# sum_rev1_4.net
KiCad netlist of a schematic drawn in EAGLE
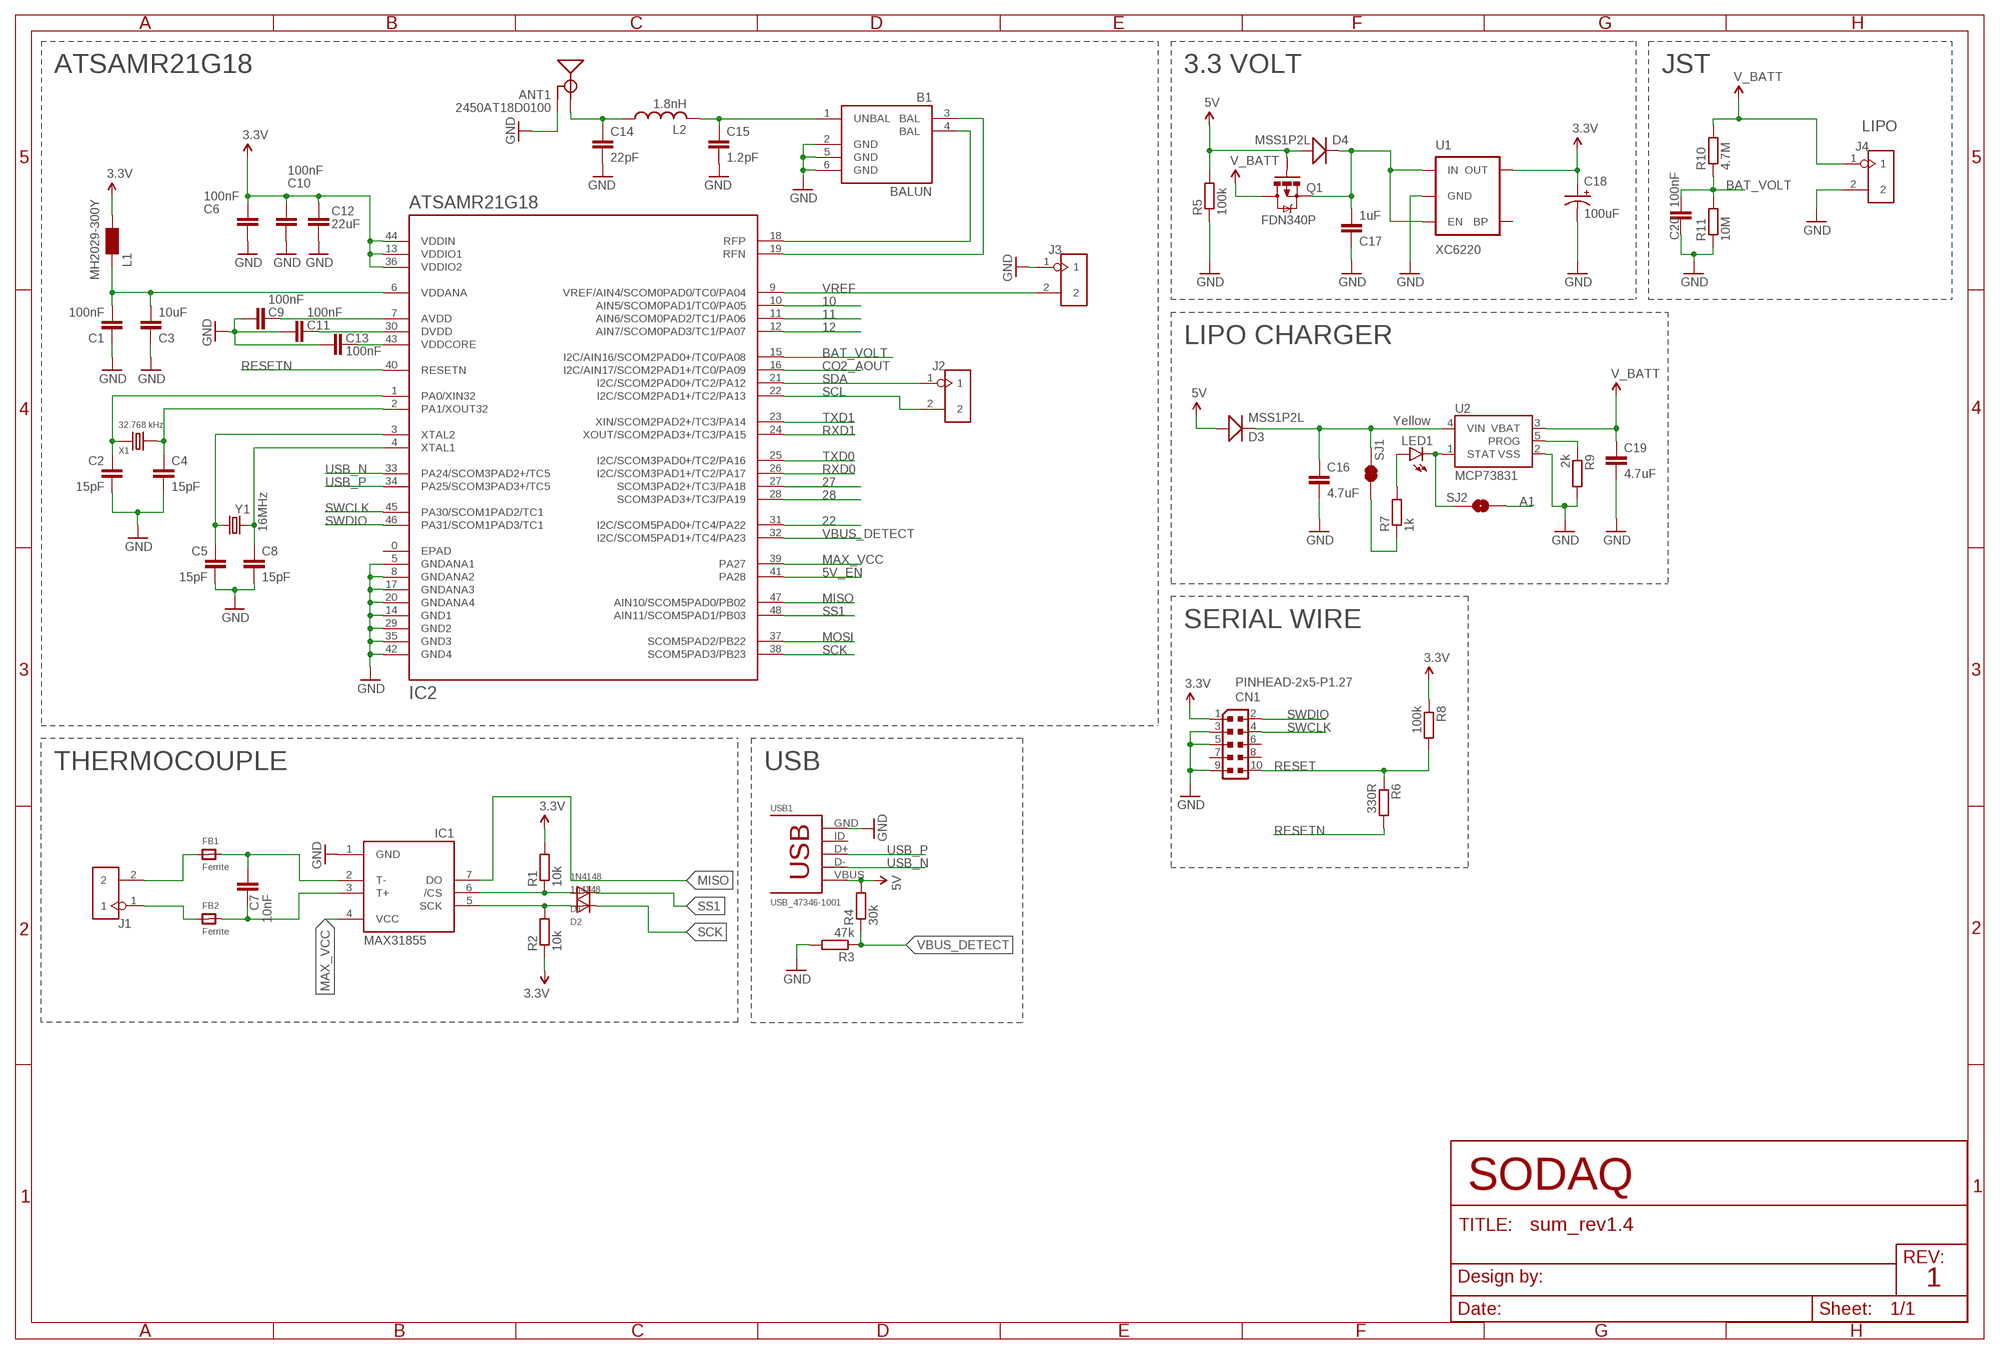
[diagram p0: schematic, sheet 1]

(export (version "E")
  (design (tool "Eeschema 10.0.6"))
  (components
    (comp (ref "ANT1")
      (value "2450AT18D0100")
      (footprint "eagle-import:2450AT18D0100")
      (libsource (lib "eagle-import") (part "2450AT18D0100"))
    )
    (comp (ref "B1")
      (value "BALUN")
      (footprint "eagle-import:BALUN")
      (libsource (lib "eagle-import") (part "BALUN"))
    )
    (comp (ref "C1")
      (value "100nF")
      (footprint "eagle-import:C0402")
      (libsource (lib "eagle-import") (part "C_0402"))
    )
    (comp (ref "C2")
      (value "15pF")
      (footprint "eagle-import:C0402")
      (libsource (lib "eagle-import") (part "C_0402"))
    )
    (comp (ref "C3")
      (value "10uF")
      (footprint "eagle-import:C0402")
      (libsource (lib "eagle-import") (part "C_0402"))
    )
    (comp (ref "C4")
      (value "15pF")
      (footprint "eagle-import:C0402")
      (libsource (lib "eagle-import") (part "C_0402"))
    )
    (comp (ref "C5")
      (value "15pF")
      (footprint "eagle-import:C0402")
      (libsource (lib "eagle-import") (part "C_0402"))
    )
    (comp (ref "C6")
      (value "100nF")
      (footprint "eagle-import:C0402")
      (libsource (lib "eagle-import") (part "C_0402"))
    )
    (comp (ref "C7")
      (value "10nF")
      (footprint "eagle-import:C0402")
      (libsource (lib "eagle-import") (part "C_0402"))
    )
    (comp (ref "C8")
      (value "15pF")
      (footprint "eagle-import:C0402")
      (libsource (lib "eagle-import") (part "C_0402"))
    )
    (comp (ref "C9")
      (value "100nF")
      (footprint "eagle-import:C0402")
      (libsource (lib "eagle-import") (part "C_0402"))
    )
    (comp (ref "C10")
      (value "100nF")
      (footprint "eagle-import:C0402")
      (libsource (lib "eagle-import") (part "C_0402"))
    )
    (comp (ref "C11")
      (value "100nF")
      (footprint "eagle-import:C0402")
      (libsource (lib "eagle-import") (part "C_0402"))
    )
    (comp (ref "C12")
      (value "22uF")
      (footprint "eagle-import:0805")
      (libsource (lib "eagle-import") (part "CAP0805"))
    )
    (comp (ref "C13")
      (value "100nF")
      (footprint "eagle-import:C0402")
      (libsource (lib "eagle-import") (part "C_0402"))
    )
    (comp (ref "C14")
      (value "22pF")
      (footprint "eagle-import:C0402")
      (libsource (lib "eagle-import") (part "C_0402"))
    )
    (comp (ref "C15")
      (value "1.2pF")
      (footprint "eagle-import:C0402")
      (libsource (lib "eagle-import") (part "C_0402"))
    )
    (comp (ref "C16")
      (value "4.7uF")
      (footprint "eagle-import:C0603")
      (libsource (lib "eagle-import") (part "C_0603"))
    )
    (comp (ref "C17")
      (value "1uF")
      (footprint "eagle-import:C0603")
      (libsource (lib "eagle-import") (part "C_0603"))
    )
    (comp (ref "C18")
      (value "100uF")
      (footprint "eagle-import:EIA3216")
      (libsource (lib "eagle-import") (part "CAP_POL1206"))
    )
    (comp (ref "C19")
      (value "4.7uF")
      (footprint "eagle-import:C0603")
      (libsource (lib "eagle-import") (part "C_0603"))
    )
    (comp (ref "C20")
      (value "100nF")
      (footprint "eagle-import:C0402")
      (libsource (lib "eagle-import") (part "C_0402"))
    )
    (comp (ref "CN1")
      (value "PINHEAD-2x5-P1.27")
      (footprint "eagle-import:PINHEAD_2X05_127")
      (libsource (lib "eagle-import") (part "0171_PH127-205DF055G00AROUND-PADS"))
    )
    (comp (ref "D1")
      (value "1N4148")
      (footprint "eagle-import:SOD-323F")
      (libsource (lib "eagle-import") (part "DIODESOD-323F"))
    )
    (comp (ref "D2")
      (value "1n4148")
      (footprint "eagle-import:SOD-323F")
      (libsource (lib "eagle-import") (part "DIODESOD-323F"))
    )
    (comp (ref "D3")
      (value "MSS1P2L")
      (footprint "eagle-import:D1005")
      (libsource (lib "eagle-import") (part "D'1005'"))
    )
    (comp (ref "D4")
      (value "MSS1P2L")
      (footprint "eagle-import:D1005")
      (libsource (lib "eagle-import") (part "D'1005'"))
    )
    (comp (ref "FB1")
      (value "Ferrite")
      (footprint "eagle-import:_0805")
      (libsource (lib "eagle-import") (part "FERRITE_0805"))
    )
    (comp (ref "FB2")
      (value "Ferrite")
      (footprint "eagle-import:_0805")
      (libsource (lib "eagle-import") (part "FERRITE_0805"))
    )
    (comp (ref "IC1")
      (value "MAX31855")
      (footprint "eagle-import:SO08")
      (libsource (lib "eagle-import") (part "MAX6675"))
    )
    (comp (ref "IC2")
      (value "ATSAMR21G18")
      (footprint "eagle-import:QFN48_SMALL-CPAD")
      (libsource (lib "eagle-import") (part "ATSAMR21G18"))
    )
    (comp (ref "J1")
      (value "HEADER-2P-2.0")
      (footprint "eagle-import:2P-2.0")
      (libsource (lib "eagle-import") (part "HEADER-2P-2.0"))
    )
    (comp (ref "J2")
      (value "HEADER-2P-2.0")
      (footprint "eagle-import:2P-2.0")
      (libsource (lib "eagle-import") (part "HEADER-2P-2.0"))
    )
    (comp (ref "J3")
      (value "HEADER-2P-2.0")
      (footprint "eagle-import:2P-2.0")
      (libsource (lib "eagle-import") (part "HEADER-2P-2.0"))
    )
    (comp (ref "J4")
      (value "HEADER-2P-2.0")
      (footprint "eagle-import:2P-2.0")
      (libsource (lib "eagle-import") (part "HEADER-2P-2.0"))
    )
    (comp (ref "L1")
      (value "MH2029-300Y")
      (footprint "eagle-import:0805")
      (fields (field (name "PART_NUMBER") "BLM21PG300SN1D_/_MH2029-300Y"))
      (libsource (lib "eagle-import") (part "0001_BLM21PG300SN1D_/_MH2029-300Y"))
    )
    (comp (ref "L2")
      (value "1.8nH")
      (footprint "eagle-import:L0402")
      (libsource (lib "eagle-import") (part "L_0402"))
    )
    (comp (ref "LED1")
      (value "Yellow")
      (footprint "eagle-import:LED-0603")
      (libsource (lib "eagle-import") (part "LED0603"))
    )
    (comp (ref "Q1")
      (value "FDN340P")
      (footprint "eagle-import:SOT23-S-PADS")
      (libsource (lib "eagle-import") (part "MOSFET-P-CHANNELSMALL"))
    )
    (comp (ref "R1")
      (value "10k")
      (footprint "eagle-import:R0402")
      (libsource (lib "eagle-import") (part "R_0402"))
    )
    (comp (ref "R2")
      (value "10k")
      (footprint "eagle-import:R0402")
      (libsource (lib "eagle-import") (part "R_0402"))
    )
    (comp (ref "R3")
      (value "47k")
      (footprint "eagle-import:R0402")
      (libsource (lib "eagle-import") (part "R_0402"))
    )
    (comp (ref "R4")
      (value "30k")
      (footprint "eagle-import:R0402")
      (libsource (lib "eagle-import") (part "R_0402"))
    )
    (comp (ref "R5")
      (value "100k")
      (footprint "eagle-import:R0402")
      (libsource (lib "eagle-import") (part "R_0402"))
    )
    (comp (ref "R6")
      (value "330R")
      (footprint "eagle-import:R0402")
      (libsource (lib "eagle-import") (part "R_0402"))
    )
    (comp (ref "R7")
      (value "1k")
      (footprint "eagle-import:R0402")
      (libsource (lib "eagle-import") (part "R_0402"))
    )
    (comp (ref "R8")
      (value "100k")
      (footprint "eagle-import:R0402")
      (libsource (lib "eagle-import") (part "R_0402"))
    )
    (comp (ref "R9")
      (value "2k")
      (footprint "eagle-import:R0402")
      (libsource (lib "eagle-import") (part "R_0402"))
    )
    (comp (ref "R10")
      (value "4.7M")
      (footprint "eagle-import:R0402")
      (libsource (lib "eagle-import") (part "R_0402"))
    )
    (comp (ref "R11")
      (value "10M")
      (footprint "eagle-import:R0402")
      (libsource (lib "eagle-import") (part "R_0402"))
    )
    (comp (ref "SJ1")
      (value "SOLDERJUMPERNC2")
      (footprint "eagle-import:SJ_2S-NOTRACE")
      (libsource (lib "eagle-import") (part "SOLDERJUMPERNC2"))
    )
    (comp (ref "SJ2")
      (value "SOLDERJUMPERNO")
      (footprint "eagle-import:SJ_2S-NO")
      (libsource (lib "eagle-import") (part "SOLDERJUMPERNO"))
    )
    (comp (ref "U1")
      (value "XC6220")
      (footprint "eagle-import:SOT23-5")
      (libsource (lib "eagle-import") (part "V_REG_LDOSMD"))
    )
    (comp (ref "U2")
      (value "MCP73831")
      (footprint "eagle-import:SOT23-5")
      (libsource (lib "eagle-import") (part "MCP73831"))
    )
    (comp (ref "USB1")
      (value "USB_47346-1001")
      (footprint "eagle-import:USB_47346-1001")
      (libsource (lib "eagle-import") (part "USB_47346-1001"))
    )
    (comp (ref "X1")
      (value "32.768 kHz")
      (footprint "eagle-import:2P-SMD-3.2X1.5")
      (libsource (lib "eagle-import") (part "CRYSTAL-3215"))
    )
    (comp (ref "Y1")
      (value "16MHz")
      (footprint "eagle-import:CRYSTAL-SMD-5X3")
      (libsource (lib "eagle-import") (part "CRYSTAL5X3"))
    )
  )
  (nets
    (net (code "1") (name "/5V_EN") (class "Default")
      (node (ref "IC2") (pin "41") (pinfunction "PA28_41") (pintype "bidirectional"))
    )
    (net (code "2") (name "/10") (class "Default")
      (node (ref "IC2") (pin "10") (pinfunction "AIN5/SCOM0PAD1/TC0/PA05_10") (pintype "bidirectional"))
    )
    (net (code "3") (name "/11") (class "Default")
      (node (ref "IC2") (pin "11") (pinfunction "AIN6/SCOM0PAD2/TC1/PA06_11") (pintype "bidirectional"))
    )
    (net (code "4") (name "/12") (class "Default")
      (node (ref "IC2") (pin "12") (pinfunction "AIN7/SCOM0PAD3/TC1/PA07_12") (pintype "bidirectional"))
    )
    (net (code "5") (name "/22") (class "Default")
      (node (ref "IC2") (pin "31") (pinfunction "I2C/SCOM5PAD0+/TC4/PA22_31") (pintype "bidirectional"))
    )
    (net (code "6") (name "/27") (class "Default")
      (node (ref "IC2") (pin "27") (pinfunction "SCOM3PAD2+/TC3/PA18_27") (pintype "bidirectional"))
    )
    (net (code "7") (name "/28") (class "Default")
      (node (ref "IC2") (pin "28") (pinfunction "SCOM3PAD3+/TC3/PA19_28") (pintype "bidirectional"))
    )
    (net (code "8") (name "/A1") (class "Default")
      (node (ref "SJ2") (pin "1") (pinfunction "1_1") (pintype "passive"))
    )
    (net (code "9") (name "/BAT_VOLT") (class "Default")
      (node (ref "C20") (pin "2") (pinfunction "2_2") (pintype "passive"))
      (node (ref "IC2") (pin "15") (pinfunction "I2C/AIN16/SCOM2PAD0+/TC0/PA08_15") (pintype "bidirectional"))
      (node (ref "R10") (pin "1") (pinfunction "1_1") (pintype "passive"))
      (node (ref "R11") (pin "2") (pinfunction "2_2") (pintype "passive"))
    )
    (net (code "10") (name "/CO2_AOUT") (class "Default")
      (node (ref "IC2") (pin "16") (pinfunction "I2C/AIN17/SCOM2PAD1+/TC0/PA09_16") (pintype "bidirectional"))
    )
    (net (code "11") (name "/EPAD") (class "Default")
      (node (ref "IC2") (pin "0") (pinfunction "EPAD_0") (pintype "power_in"))
    )
    (net (code "12") (name "/MOSI") (class "Default")
      (node (ref "IC2") (pin "37") (pinfunction "SCOM5PAD2/PB22_37") (pintype "bidirectional"))
    )
    (net (code "13") (name "/RESET") (class "Default")
      (node (ref "CN1") (pin "10") (pinfunction "10_10") (pintype "passive"))
      (node (ref "R6") (pin "1") (pinfunction "1_1") (pintype "passive"))
      (node (ref "R8") (pin "2") (pinfunction "2_2") (pintype "passive"))
    )
    (net (code "14") (name "/RESETN") (class "Default")
      (node (ref "IC2") (pin "40") (pinfunction "RESETN_40") (pintype "bidirectional"))
      (node (ref "R6") (pin "2") (pinfunction "2_2") (pintype "passive"))
    )
    (net (code "15") (name "/RXD0") (class "Default")
      (node (ref "IC2") (pin "26") (pinfunction "I2C/SCOM3PAD1+/TC2/PA17_26") (pintype "bidirectional"))
    )
    (net (code "16") (name "/RXD1") (class "Default")
      (node (ref "IC2") (pin "24") (pinfunction "XOUT/SCOM2PAD3+/TC3/PA15_24") (pintype "bidirectional"))
    )
    (net (code "17") (name "/SCL") (class "Default")
      (node (ref "IC2") (pin "22") (pinfunction "I2C/SCOM2PAD1+/TC2/PA13_22") (pintype "bidirectional"))
      (node (ref "J2") (pin "2") (pinfunction "2_2") (pintype "bidirectional"))
    )
    (net (code "18") (name "/SDA") (class "Default")
      (node (ref "IC2") (pin "21") (pinfunction "I2C/SCOM2PAD0+/TC2/PA12_21") (pintype "bidirectional"))
      (node (ref "J2") (pin "1") (pinfunction "1_1") (pintype "bidirectional"))
    )
    (net (code "19") (name "/SWCLK") (class "Default")
      (node (ref "CN1") (pin "4") (pinfunction "4_4") (pintype "passive"))
      (node (ref "IC2") (pin "45") (pinfunction "PA30/SCOM1PAD2/TC1_45") (pintype "bidirectional"))
    )
    (net (code "20") (name "/SWDIO") (class "Default")
      (node (ref "CN1") (pin "2") (pinfunction "2_2") (pintype "passive"))
      (node (ref "IC2") (pin "46") (pinfunction "PA31/SCOM1PAD3/TC1_46") (pintype "bidirectional"))
    )
    (net (code "21") (name "/TXD0") (class "Default")
      (node (ref "IC2") (pin "25") (pinfunction "I2C/SCOM3PAD0+/TC2/PA16_25") (pintype "bidirectional"))
    )
    (net (code "22") (name "/TXD1") (class "Default")
      (node (ref "IC2") (pin "23") (pinfunction "XIN/SCOM2PAD2+/TC3/PA14_23") (pintype "bidirectional"))
    )
    (net (code "23") (name "/USB_N") (class "Default")
      (node (ref "IC2") (pin "33") (pinfunction "PA24/SCOM3PAD2+/TC5_33") (pintype "bidirectional"))
      (node (ref "USB1") (pin "D-") (pinfunction "D-_D-") (pintype "bidirectional"))
    )
    (net (code "24") (name "/USB_P") (class "Default")
      (node (ref "IC2") (pin "34") (pinfunction "PA25/SCOM3PAD3+/TC5_34") (pintype "bidirectional"))
      (node (ref "USB1") (pin "D+") (pinfunction "D+_D+") (pintype "bidirectional"))
    )
    (net (code "25") (name "/VREF") (class "Default")
      (node (ref "IC2") (pin "9") (pinfunction "VREF/AIN4/SCOM0PAD0/TC0/PA04_9") (pintype "bidirectional"))
      (node (ref "J3") (pin "2") (pinfunction "2_2") (pintype "bidirectional"))
    )
    (net (code "26") (name "3.3V") (class "Default")
      (node (ref "C10") (pin "2") (pinfunction "2_2") (pintype "passive"))
      (node (ref "C12") (pin "1") (pinfunction "1_1") (pintype "passive"))
      (node (ref "C18") (pin "A") (pinfunction "+_A") (pintype "passive"))
      (node (ref "C6") (pin "2") (pinfunction "2_2") (pintype "passive"))
      (node (ref "CN1") (pin "1") (pinfunction "1_1") (pintype "passive"))
      (node (ref "IC2") (pin "13") (pinfunction "VDDIO1_13") (pintype "power_in"))
      (node (ref "IC2") (pin "36") (pinfunction "VDDIO2_36") (pintype "power_in"))
      (node (ref "IC2") (pin "44") (pinfunction "VDDIN_44") (pintype "power_in"))
      (node (ref "L1") (pin "2") (pinfunction "2_2") (pintype "passive"))
      (node (ref "R1") (pin "2") (pinfunction "2_2") (pintype "passive"))
      (node (ref "R2") (pin "1") (pinfunction "1_1") (pintype "passive"))
      (node (ref "R8") (pin "1") (pinfunction "1_1") (pintype "passive"))
      (node (ref "U1") (pin "5") (pinfunction "OUT_5") (pintype "passive"))
    )
    (net (code "27") (name "5V") (class "Default")
      (node (ref "D3") (pin "+") (pinfunction "+_+") (pintype "passive"))
      (node (ref "D4") (pin "+") (pinfunction "+_+") (pintype "passive"))
      (node (ref "Q1") (pin "1") (pinfunction "G_1") (pintype "passive"))
      (node (ref "R4") (pin "2") (pinfunction "2_2") (pintype "passive"))
      (node (ref "R5") (pin "2") (pinfunction "2_2") (pintype "passive"))
      (node (ref "USB1") (pin "VBUS") (pinfunction "VBUS_VBUS") (pintype "bidirectional"))
    )
    (net (code "28") (name "GND") (class "Default")
      (node (ref "ANT1") (pin "2") (pinfunction "GND_2") (pintype "bidirectional"))
      (node (ref "ANT1") (pin "3") (pinfunction "GND_3") (pintype "bidirectional"))
      (node (ref "ANT1") (pin "4") (pinfunction "GND_4") (pintype "bidirectional"))
      (node (ref "B1") (pin "2") (pinfunction "GND_2") (pintype "bidirectional"))
      (node (ref "B1") (pin "5") (pinfunction "GND_5") (pintype "bidirectional"))
      (node (ref "B1") (pin "6") (pinfunction "GND_6") (pintype "bidirectional"))
      (node (ref "C1") (pin "2") (pinfunction "2_2") (pintype "passive"))
      (node (ref "C10") (pin "1") (pinfunction "1_1") (pintype "passive"))
      (node (ref "C11") (pin "2") (pinfunction "2_2") (pintype "passive"))
      (node (ref "C12") (pin "2") (pinfunction "2_2") (pintype "passive"))
      (node (ref "C13") (pin "2") (pinfunction "2_2") (pintype "passive"))
      (node (ref "C14") (pin "2") (pinfunction "2_2") (pintype "passive"))
      (node (ref "C15") (pin "2") (pinfunction "2_2") (pintype "passive"))
      (node (ref "C16") (pin "2") (pinfunction "2_2") (pintype "passive"))
      (node (ref "C17") (pin "1") (pinfunction "1_1") (pintype "passive"))
      (node (ref "C18") (pin "C") (pinfunction "-_C") (pintype "passive"))
      (node (ref "C19") (pin "2") (pinfunction "2_2") (pintype "passive"))
      (node (ref "C2") (pin "1") (pinfunction "1_1") (pintype "passive"))
      (node (ref "C20") (pin "1") (pinfunction "1_1") (pintype "passive"))
      (node (ref "C3") (pin "2") (pinfunction "2_2") (pintype "passive"))
      (node (ref "C4") (pin "2") (pinfunction "2_2") (pintype "passive"))
      (node (ref "C5") (pin "2") (pinfunction "2_2") (pintype "passive"))
      (node (ref "C6") (pin "1") (pinfunction "1_1") (pintype "passive"))
      (node (ref "C8") (pin "2") (pinfunction "2_2") (pintype "passive"))
      (node (ref "C9") (pin "2") (pinfunction "2_2") (pintype "passive"))
      (node (ref "CN1") (pin "3") (pinfunction "3_3") (pintype "passive"))
      (node (ref "CN1") (pin "5") (pinfunction "5_5") (pintype "passive"))
      (node (ref "CN1") (pin "9") (pinfunction "9_9") (pintype "passive"))
      (node (ref "IC1") (pin "1") (pinfunction "GND_1") (pintype "power_in"))
      (node (ref "IC2") (pin "14") (pinfunction "GND1_14") (pintype "power_in"))
      (node (ref "IC2") (pin "17") (pinfunction "GNDANA3_17") (pintype "power_in"))
      (node (ref "IC2") (pin "20") (pinfunction "GNDANA4_20") (pintype "power_in"))
      (node (ref "IC2") (pin "29") (pinfunction "GND2_29") (pintype "power_in"))
      (node (ref "IC2") (pin "35") (pinfunction "GND3_35") (pintype "power_in"))
      (node (ref "IC2") (pin "42") (pinfunction "GND4_42") (pintype "power_in"))
      (node (ref "IC2") (pin "5") (pinfunction "GNDANA1_5") (pintype "power_in"))
      (node (ref "IC2") (pin "8") (pinfunction "GNDANA2_8") (pintype "power_in"))
      (node (ref "J3") (pin "1") (pinfunction "1_1") (pintype "bidirectional"))
      (node (ref "J4") (pin "2") (pinfunction "2_2") (pintype "bidirectional"))
      (node (ref "R11") (pin "1") (pinfunction "1_1") (pintype "passive"))
      (node (ref "R3") (pin "2") (pinfunction "2_2") (pintype "passive"))
      (node (ref "R5") (pin "1") (pinfunction "1_1") (pintype "passive"))
      (node (ref "R9") (pin "2") (pinfunction "2_2") (pintype "passive"))
      (node (ref "U1") (pin "2") (pinfunction "GND_2") (pintype "input"))
      (node (ref "U2") (pin "2") (pinfunction "VSS_2") (pintype "power_in"))
      (node (ref "USB1") (pin "GND") (pinfunction "GND_GND") (pintype "bidirectional"))
    )
    (net (code "29") (name "MAX_VCC") (class "Default")
      (node (ref "IC1") (pin "4") (pinfunction "VCC_4") (pintype "power_in"))
      (node (ref "IC2") (pin "39") (pinfunction "PA27_39") (pintype "bidirectional"))
    )
    (net (code "30") (name "MISO") (class "Default")
      (node (ref "IC1") (pin "7") (pinfunction "DO_7") (pintype "output"))
      (node (ref "IC2") (pin "47") (pinfunction "AIN10/SCOM5PAD0/PB02_47") (pintype "bidirectional"))
    )
    (net (code "31") (name "Net-(ANT1-SIGNAL)") (class "Default")
      (node (ref "ANT1") (pin "1") (pinfunction "SIGNAL_1") (pintype "bidirectional"))
      (node (ref "C14") (pin "1") (pinfunction "1_1") (pintype "passive"))
      (node (ref "L2") (pin "1") (pinfunction "1_1") (pintype "passive"))
    )
    (net (code "32") (name "Net-(B1-UNBAL)") (class "Default")
      (node (ref "B1") (pin "1") (pinfunction "UNBAL_1") (pintype "bidirectional"))
      (node (ref "C15") (pin "1") (pinfunction "1_1") (pintype "passive"))
      (node (ref "L2") (pin "2") (pinfunction "2_2") (pintype "passive"))
    )
    (net (code "33") (name "Net-(FB1-P$1)") (class "Default")
      (node (ref "FB1") (pin "1") (pinfunction "P$1_1") (pintype "passive"))
      (node (ref "J1") (pin "2") (pinfunction "2_2") (pintype "bidirectional"))
    )
    (net (code "34") (name "Net-(FB1-P$2)") (class "Default")
      (node (ref "C7") (pin "2") (pinfunction "2_2") (pintype "passive"))
      (node (ref "FB1") (pin "2") (pinfunction "P$2_2") (pintype "passive"))
      (node (ref "IC1") (pin "2") (pinfunction "T-_2") (pintype "input"))
    )
    (net (code "35") (name "Net-(FB2-P$1)") (class "Default")
      (node (ref "FB2") (pin "1") (pinfunction "P$1_1") (pintype "passive"))
      (node (ref "J1") (pin "1") (pinfunction "1_1") (pintype "bidirectional"))
    )
    (net (code "36") (name "Net-(FB2-P$2)") (class "Default")
      (node (ref "C7") (pin "1") (pinfunction "1_1") (pintype "passive"))
      (node (ref "FB2") (pin "2") (pinfunction "P$2_2") (pintype "passive"))
      (node (ref "IC1") (pin "3") (pinfunction "T+_3") (pintype "input"))
    )
    (net (code "37") (name "Net-(IC1-SCK)") (class "Default")
      (node (ref "D2") (pin "A") (pinfunction "A_A") (pintype "passive"))
      (node (ref "IC1") (pin "5") (pinfunction "SCK_5") (pintype "input"))
      (node (ref "R2") (pin "2") (pinfunction "2_2") (pintype "passive"))
    )
    (net (code "38") (name "Net-(IC1-{slash}CS)") (class "Default")
      (node (ref "D1") (pin "A") (pinfunction "A_A") (pintype "passive"))
      (node (ref "IC1") (pin "6") (pinfunction "/CS_6") (pintype "input"))
      (node (ref "R1") (pin "1") (pinfunction "1_1") (pintype "passive"))
    )
    (net (code "39") (name "Net-(IC2-AVDD)") (class "Default")
      (node (ref "C9") (pin "1") (pinfunction "1_1") (pintype "passive"))
      (node (ref "IC2") (pin "7") (pinfunction "AVDD_7") (pintype "power_in"))
    )
    (net (code "40") (name "Net-(IC2-DVDD)") (class "Default")
      (node (ref "C11") (pin "1") (pinfunction "1_1") (pintype "passive"))
      (node (ref "IC2") (pin "30") (pinfunction "DVDD_30") (pintype "power_in"))
    )
    (net (code "41") (name "Net-(IC2-PA0{slash}XIN32)") (class "Default")
      (node (ref "C2") (pin "2") (pinfunction "2_2") (pintype "passive"))
      (node (ref "IC2") (pin "1") (pinfunction "PA0/XIN32_1") (pintype "bidirectional"))
      (node (ref "X1") (pin "1") (pinfunction "1_1") (pintype "passive"))
    )
    (net (code "42") (name "Net-(IC2-PA1{slash}XOUT32)") (class "Default")
      (node (ref "C4") (pin "1") (pinfunction "1_1") (pintype "passive"))
      (node (ref "IC2") (pin "2") (pinfunction "PA1/XOUT32_2") (pintype "bidirectional"))
      (node (ref "X1") (pin "2") (pinfunction "2_2") (pintype "passive"))
    )
    (net (code "43") (name "Net-(IC2-RFN)") (class "Default")
      (node (ref "B1") (pin "3") (pinfunction "BAL_3") (pintype "bidirectional"))
      (node (ref "IC2") (pin "19") (pinfunction "RFN_19") (pintype "bidirectional"))
    )
    (net (code "44") (name "Net-(IC2-RFP)") (class "Default")
      (node (ref "B1") (pin "4") (pinfunction "BAL_4") (pintype "bidirectional"))
      (node (ref "IC2") (pin "18") (pinfunction "RFP_18") (pintype "bidirectional"))
    )
    (net (code "45") (name "Net-(IC2-VDDANA)") (class "Default")
      (node (ref "C1") (pin "1") (pinfunction "1_1") (pintype "passive"))
      (node (ref "C3") (pin "1") (pinfunction "1_1") (pintype "passive"))
      (node (ref "IC2") (pin "6") (pinfunction "VDDANA_6") (pintype "power_in"))
      (node (ref "L1") (pin "1") (pinfunction "1_1") (pintype "passive"))
    )
    (net (code "46") (name "Net-(IC2-VDDCORE)") (class "Default")
      (node (ref "C13") (pin "1") (pinfunction "1_1") (pintype "passive"))
      (node (ref "IC2") (pin "43") (pinfunction "VDDCORE_43") (pintype "input"))
    )
    (net (code "47") (name "Net-(IC2-XTAL1)") (class "Default")
      (node (ref "C8") (pin "1") (pinfunction "1_1") (pintype "passive"))
      (node (ref "IC2") (pin "4") (pinfunction "XTAL1_4") (pintype "bidirectional"))
      (node (ref "Y1") (pin "3") (pinfunction "2_3") (pintype "passive"))
    )
    (net (code "48") (name "Net-(IC2-XTAL2)") (class "Default")
      (node (ref "C5") (pin "1") (pinfunction "1_1") (pintype "passive"))
      (node (ref "IC2") (pin "3") (pinfunction "XTAL2_3") (pintype "bidirectional"))
      (node (ref "Y1") (pin "1") (pinfunction "1_1") (pintype "passive"))
    )
    (net (code "49") (name "Net-(LED1-PadA)") (class "Default")
      (node (ref "LED1") (pin "A") (pinfunction "A_A") (pintype "passive"))
      (node (ref "R7") (pin "2") (pinfunction "2_2") (pintype "passive"))
    )
    (net (code "50") (name "Net-(Q1-S)") (class "Default")
      (node (ref "C17") (pin "2") (pinfunction "2_2") (pintype "passive"))
      (node (ref "D4") (pin "-") (pinfunction "-_-") (pintype "passive"))
      (node (ref "Q1") (pin "2") (pinfunction "S_2") (pintype "passive"))
      (node (ref "U1") (pin "1") (pinfunction "IN_1") (pintype "input"))
      (node (ref "U1") (pin "3") (pinfunction "EN_3") (pintype "input"))
    )
    (net (code "51") (name "Net-(R7-Pad1)") (class "Default")
      (node (ref "R7") (pin "1") (pinfunction "1_1") (pintype "passive"))
      (node (ref "SJ1") (pin "1") (pinfunction "1_1") (pintype "passive"))
    )
    (net (code "52") (name "Net-(U2-PROG)") (class "Default")
      (node (ref "R9") (pin "1") (pinfunction "1_1") (pintype "passive"))
      (node (ref "U2") (pin "5") (pinfunction "PROG_5") (pintype "input"))
    )
    (net (code "53") (name "Net-(U2-STAT)") (class "Default")
      (node (ref "LED1") (pin "C") (pinfunction "C_C") (pintype "passive"))
      (node (ref "SJ2") (pin "2") (pinfunction "2_2") (pintype "passive"))
      (node (ref "U2") (pin "1") (pinfunction "STAT_1") (pintype "output"))
    )
    (net (code "54") (name "Net-(U2-VIN)") (class "Default")
      (node (ref "C16") (pin "1") (pinfunction "1_1") (pintype "passive"))
      (node (ref "D3") (pin "-") (pinfunction "-_-") (pintype "passive"))
      (node (ref "SJ1") (pin "2") (pinfunction "2_2") (pintype "passive"))
      (node (ref "U2") (pin "4") (pinfunction "VIN_4") (pintype "power_in"))
    )
    (net (code "55") (name "SCK") (class "Default")
      (node (ref "D2") (pin "C") (pinfunction "C_C") (pintype "passive"))
      (node (ref "IC2") (pin "38") (pinfunction "SCOM5PAD3/PB23_38") (pintype "bidirectional"))
    )
    (net (code "56") (name "SS1") (class "Default")
      (node (ref "D1") (pin "C") (pinfunction "C_C") (pintype "passive"))
      (node (ref "IC2") (pin "48") (pinfunction "AIN11/SCOM5PAD1/PB03_48") (pintype "bidirectional"))
    )
    (net (code "57") (name "VBUS_DETECT") (class "Default")
      (node (ref "IC2") (pin "32") (pinfunction "I2C/SCOM5PAD1+/TC4/PA23_32") (pintype "bidirectional"))
      (node (ref "R3") (pin "1") (pinfunction "1_1") (pintype "passive"))
      (node (ref "R4") (pin "1") (pinfunction "1_1") (pintype "passive"))
    )
    (net (code "58") (name "V_BATT") (class "Default")
      (node (ref "C19") (pin "1") (pinfunction "1_1") (pintype "passive"))
      (node (ref "J4") (pin "1") (pinfunction "1_1") (pintype "bidirectional"))
      (node (ref "Q1") (pin "3") (pinfunction "D_3") (pintype "passive"))
      (node (ref "R10") (pin "2") (pinfunction "2_2") (pintype "passive"))
      (node (ref "U2") (pin "3") (pinfunction "VBAT_3") (pintype "power_in"))
    )
    (net (code "59") (name "unconnected-(CN1-Pad6)") (class "Default")
      (node (ref "CN1") (pin "6") (pinfunction "6_6") (pintype "passive"))
    )
    (net (code "60") (name "unconnected-(CN1-Pad7)") (class "Default")
      (node (ref "CN1") (pin "7") (pinfunction "7_7") (pintype "passive"))
    )
    (net (code "61") (name "unconnected-(CN1-Pad8)") (class "Default")
      (node (ref "CN1") (pin "8") (pinfunction "8_8") (pintype "passive"))
    )
    (net (code "62") (name "unconnected-(U1-BP-Pad4)") (class "Default")
      (node (ref "U1") (pin "4") (pinfunction "BP_4") (pintype "input"))
    )
    (net (code "63") (name "unconnected-(USB1-PadID)") (class "Default")
      (node (ref "USB1") (pin "ID") (pinfunction "ID_ID") (pintype "bidirectional"))
    )
  )
)
